# Remute-RF-FT.net
KiCad netlist of a schematic drawn in Altium Designer
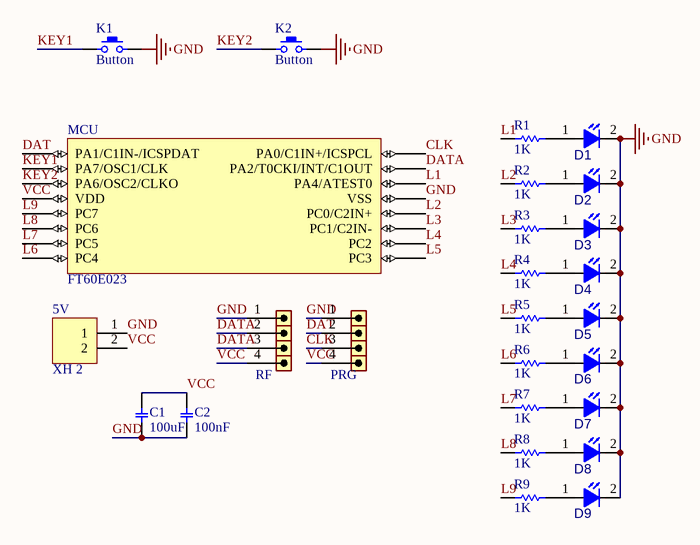
[diagram p0: Remute-RF-FT.SchDoc]

(export (version "E")
  (design (tool "Eeschema 10.0.6"))
  (components
    (comp (ref "5V")
      (value "XH 2")
      (footprint "XH 2 PIN ( White )")
      (description "Conector XH 2 Pin")
      (libsource (lib "XH Connector") (part "Conector XH 2 Pin"))
    )
    (comp (ref "C1")
      (value "100uF")
      (footprint "C1206")
      (description "Capacitor C SMD 1206")
      (fields (field (name "Comment") "Capacitor SMD 1206"))
      (libsource (lib "Capacitor") (part "Capacitor SMD 1206"))
    )
    (comp (ref "C2")
      (value "100nF")
      (footprint "C1206")
      (description "Capacitor C SMD 1206")
      (fields (field (name "Comment") "Capacitor SMD 1206"))
      (libsource (lib "Capacitor") (part "Capacitor SMD 1206"))
    )
    (comp (ref "D1")
      (value "LED SMD 1206")
      (footprint "LED SMD 1206 (Blue)")
      (libsource (lib "LED") (part "LED SMD 1206"))
    )
    (comp (ref "D2")
      (value "LED SMD 1206")
      (footprint "LED SMD 1206 (Blue)")
      (libsource (lib "LED") (part "LED SMD 1206"))
    )
    (comp (ref "D3")
      (value "LED SMD 1206")
      (footprint "LED SMD 1206 (Blue)")
      (libsource (lib "LED") (part "LED SMD 1206"))
    )
    (comp (ref "D4")
      (value "LED SMD 1206")
      (footprint "LED SMD 1206 (Blue)")
      (libsource (lib "LED") (part "LED SMD 1206"))
    )
    (comp (ref "D5")
      (value "LED SMD 1206")
      (footprint "LED SMD 1206 (Blue)")
      (libsource (lib "LED") (part "LED SMD 1206"))
    )
    (comp (ref "D6")
      (value "LED SMD 1206")
      (footprint "LED SMD 1206 (Blue)")
      (libsource (lib "LED") (part "LED SMD 1206"))
    )
    (comp (ref "D7")
      (value "LED SMD 1206")
      (footprint "LED SMD 1206 (Blue)")
      (libsource (lib "LED") (part "LED SMD 1206"))
    )
    (comp (ref "D8")
      (value "LED SMD 1206")
      (footprint "LED SMD 1206 (Blue)")
      (libsource (lib "LED") (part "LED SMD 1206"))
    )
    (comp (ref "D9")
      (value "LED SMD 1206")
      (footprint "LED SMD 1206 (Blue)")
      (libsource (lib "LED") (part "LED SMD 1206"))
    )
    (comp (ref "K1")
      (value "Button")
      (footprint "BUTTON")
      (fields
        (field (name "MANUFACTURER") "Panasonic")
        (field (name "MANUFACTURER PART NUMBER") "EVQ-PE605T")
      )
      (libsource (lib "LIBM") (part "BUTTON-6.3.4-SMD"))
    )
    (comp (ref "K2")
      (value "Button")
      (footprint "BUTTON")
      (fields
        (field (name "MANUFACTURER") "Panasonic")
        (field (name "MANUFACTURER PART NUMBER") "EVQ-PE605T")
      )
      (libsource (lib "LIBM") (part "BUTTON-6.3.4-SMD"))
    )
    (comp (ref "MCU") (value "FT60E023") (footprint "SSOP-16") (libsource (lib "HOLTEK") (part "FT60E023")))
    (comp (ref "PRG")
      (value "Female Header Single 4")
      (footprint "HDR_F_1X4")
      (description "Female, pitch: 2.54mm")
      (libsource (lib "Header") (part "Female Header Single 4"))
    )
    (comp (ref "R1")
      (value "1K")
      (footprint "R0805")
      (description "Resistor SMD 0805")
      (libsource (lib "Resistor") (part "Resistor SMD 0805"))
    )
    (comp (ref "R2")
      (value "1K")
      (footprint "R0805")
      (description "Resistor SMD 0805")
      (libsource (lib "Resistor") (part "Resistor SMD 0805"))
    )
    (comp (ref "R3")
      (value "1K")
      (footprint "R0805")
      (description "Resistor SMD 0805")
      (libsource (lib "Resistor") (part "Resistor SMD 0805"))
    )
    (comp (ref "R4")
      (value "1K")
      (footprint "R0805")
      (description "Resistor SMD 0805")
      (libsource (lib "Resistor") (part "Resistor SMD 0805"))
    )
    (comp (ref "R5")
      (value "1K")
      (footprint "R0805")
      (description "Resistor SMD 0805")
      (libsource (lib "Resistor") (part "Resistor SMD 0805"))
    )
    (comp (ref "R6")
      (value "1K")
      (footprint "R0805")
      (description "Resistor SMD 0805")
      (libsource (lib "Resistor") (part "Resistor SMD 0805"))
    )
    (comp (ref "R7")
      (value "1K")
      (footprint "R0805")
      (description "Resistor SMD 0805")
      (libsource (lib "Resistor") (part "Resistor SMD 0805"))
    )
    (comp (ref "R8")
      (value "1K")
      (footprint "R0805")
      (description "Resistor SMD 0805")
      (libsource (lib "Resistor") (part "Resistor SMD 0805"))
    )
    (comp (ref "R9")
      (value "1K")
      (footprint "R0805")
      (description "Resistor SMD 0805")
      (libsource (lib "Resistor") (part "Resistor SMD 0805"))
    )
    (comp (ref "RF")
      (value "Female Header Single 4")
      (footprint "HDR_F_1X4")
      (description "Female, pitch: 2.54mm")
      (libsource (lib "Header") (part "Female Header Single 4"))
    )
  )
  (nets
    (net (code "1") (name "/CLK") (class "Default")
      (node (ref "MCU") (pin "16") (pinfunction "PA0/C1IN+/ICSPCL_16") (pintype "bidirectional"))
      (node (ref "PRG") (pin "3") (pinfunction "3_3") (pintype "passive"))
    )
    (net (code "2") (name "/DAT") (class "Default")
      (node (ref "MCU") (pin "1") (pinfunction "PA1/C1IN-/ICSPDAT_1") (pintype "bidirectional"))
      (node (ref "PRG") (pin "2") (pinfunction "2_2") (pintype "passive"))
    )
    (net (code "3") (name "/DATA") (class "Default")
      (node (ref "MCU") (pin "15") (pinfunction "PA2/T0CKI/INT/C1OUT_15") (pintype "bidirectional"))
      (node (ref "RF") (pin "2") (pinfunction "2_2") (pintype "passive"))
      (node (ref "RF") (pin "3") (pinfunction "3_3") (pintype "passive"))
    )
    (net (code "4") (name "/KEY1") (class "Default")
      (node (ref "K1") (pin "1") (pinfunction "1_1") (pintype "passive"))
      (node (ref "MCU") (pin "2") (pinfunction "PA7/OSC1/CLK_2") (pintype "bidirectional"))
    )
    (net (code "5") (name "/KEY2") (class "Default")
      (node (ref "K2") (pin "1") (pinfunction "1_1") (pintype "passive"))
      (node (ref "MCU") (pin "3") (pinfunction "PA6/OSC2/CLKO_3") (pintype "bidirectional"))
    )
    (net (code "6") (name "/L1") (class "Default")
      (node (ref "MCU") (pin "14") (pinfunction "PA4/ATEST0_14") (pintype "bidirectional"))
      (node (ref "R1") (pin "1") (pinfunction "1_1") (pintype "passive"))
    )
    (net (code "7") (name "/L2") (class "Default")
      (node (ref "MCU") (pin "12") (pinfunction "PC0/C2IN+_12") (pintype "bidirectional"))
      (node (ref "R2") (pin "1") (pinfunction "1_1") (pintype "passive"))
    )
    (net (code "8") (name "/L3") (class "Default")
      (node (ref "MCU") (pin "11") (pinfunction "PC1/C2IN-_11") (pintype "bidirectional"))
      (node (ref "R3") (pin "1") (pinfunction "1_1") (pintype "passive"))
    )
    (net (code "9") (name "/L4") (class "Default")
      (node (ref "MCU") (pin "10") (pinfunction "PC2_10") (pintype "bidirectional"))
      (node (ref "R4") (pin "1") (pinfunction "1_1") (pintype "passive"))
    )
    (net (code "10") (name "/L5") (class "Default")
      (node (ref "MCU") (pin "9") (pinfunction "PC3_9") (pintype "bidirectional"))
      (node (ref "R5") (pin "1") (pinfunction "1_1") (pintype "passive"))
    )
    (net (code "11") (name "/L6") (class "Default")
      (node (ref "MCU") (pin "8") (pinfunction "PC4_8") (pintype "bidirectional"))
      (node (ref "R6") (pin "1") (pinfunction "1_1") (pintype "passive"))
    )
    (net (code "12") (name "/L7") (class "Default")
      (node (ref "MCU") (pin "7") (pinfunction "PC5_7") (pintype "bidirectional"))
      (node (ref "R7") (pin "1") (pinfunction "1_1") (pintype "passive"))
    )
    (net (code "13") (name "/L8") (class "Default")
      (node (ref "MCU") (pin "6") (pinfunction "PC6_6") (pintype "bidirectional"))
      (node (ref "R8") (pin "1") (pinfunction "1_1") (pintype "passive"))
    )
    (net (code "14") (name "/L9") (class "Default")
      (node (ref "MCU") (pin "5") (pinfunction "PC7_5") (pintype "bidirectional"))
      (node (ref "R9") (pin "1") (pinfunction "1_1") (pintype "passive"))
    )
    (net (code "15") (name "/VCC") (class "Default")
      (node (ref "5V") (pin "2") (pinfunction "2_2") (pintype "passive"))
      (node (ref "C1") (pin "2") (pinfunction "2_2") (pintype "passive"))
      (node (ref "C2") (pin "2") (pinfunction "2_2") (pintype "passive"))
      (node (ref "MCU") (pin "4") (pinfunction "VDD_4") (pintype "bidirectional"))
      (node (ref "PRG") (pin "4") (pinfunction "4_4") (pintype "passive"))
      (node (ref "RF") (pin "4") (pinfunction "4_4") (pintype "passive"))
    )
    (net (code "16") (name "GND") (class "Default")
      (node (ref "5V") (pin "1") (pinfunction "1_1") (pintype "passive"))
      (node (ref "C1") (pin "1") (pinfunction "1_1") (pintype "passive"))
      (node (ref "C2") (pin "1") (pinfunction "1_1") (pintype "passive"))
      (node (ref "D1") (pin "2") (pinfunction "CATHODE_2") (pintype "passive"))
      (node (ref "D2") (pin "2") (pinfunction "CATHODE_2") (pintype "passive"))
      (node (ref "D3") (pin "2") (pinfunction "CATHODE_2") (pintype "passive"))
      (node (ref "D4") (pin "2") (pinfunction "CATHODE_2") (pintype "passive"))
      (node (ref "D5") (pin "2") (pinfunction "CATHODE_2") (pintype "passive"))
      (node (ref "D6") (pin "2") (pinfunction "CATHODE_2") (pintype "passive"))
      (node (ref "D7") (pin "2") (pinfunction "CATHODE_2") (pintype "passive"))
      (node (ref "D8") (pin "2") (pinfunction "CATHODE_2") (pintype "passive"))
      (node (ref "D9") (pin "2") (pinfunction "CATHODE_2") (pintype "passive"))
      (node (ref "K1") (pin "2") (pinfunction "2_2") (pintype "passive"))
      (node (ref "K2") (pin "2") (pinfunction "2_2") (pintype "passive"))
      (node (ref "MCU") (pin "13") (pinfunction "VSS_13") (pintype "bidirectional"))
      (node (ref "PRG") (pin "1") (pinfunction "1_1") (pintype "passive"))
      (node (ref "RF") (pin "1") (pinfunction "1_1") (pintype "passive"))
    )
    (net (code "17") (name "Net-(D1-ANODE)") (class "Default")
      (node (ref "D1") (pin "1") (pinfunction "ANODE_1") (pintype "passive"))
      (node (ref "R1") (pin "2") (pinfunction "2_2") (pintype "passive"))
    )
    (net (code "18") (name "Net-(D2-ANODE)") (class "Default")
      (node (ref "D2") (pin "1") (pinfunction "ANODE_1") (pintype "passive"))
      (node (ref "R2") (pin "2") (pinfunction "2_2") (pintype "passive"))
    )
    (net (code "19") (name "Net-(D3-ANODE)") (class "Default")
      (node (ref "D3") (pin "1") (pinfunction "ANODE_1") (pintype "passive"))
      (node (ref "R3") (pin "2") (pinfunction "2_2") (pintype "passive"))
    )
    (net (code "20") (name "Net-(D4-ANODE)") (class "Default")
      (node (ref "D4") (pin "1") (pinfunction "ANODE_1") (pintype "passive"))
      (node (ref "R4") (pin "2") (pinfunction "2_2") (pintype "passive"))
    )
    (net (code "21") (name "Net-(D5-ANODE)") (class "Default")
      (node (ref "D5") (pin "1") (pinfunction "ANODE_1") (pintype "passive"))
      (node (ref "R5") (pin "2") (pinfunction "2_2") (pintype "passive"))
    )
    (net (code "22") (name "Net-(D6-ANODE)") (class "Default")
      (node (ref "D6") (pin "1") (pinfunction "ANODE_1") (pintype "passive"))
      (node (ref "R6") (pin "2") (pinfunction "2_2") (pintype "passive"))
    )
    (net (code "23") (name "Net-(D7-ANODE)") (class "Default")
      (node (ref "D7") (pin "1") (pinfunction "ANODE_1") (pintype "passive"))
      (node (ref "R7") (pin "2") (pinfunction "2_2") (pintype "passive"))
    )
    (net (code "24") (name "Net-(D8-ANODE)") (class "Default")
      (node (ref "D8") (pin "1") (pinfunction "ANODE_1") (pintype "passive"))
      (node (ref "R8") (pin "2") (pinfunction "2_2") (pintype "passive"))
    )
    (net (code "25") (name "Net-(D9-ANODE)") (class "Default")
      (node (ref "D9") (pin "1") (pinfunction "ANODE_1") (pintype "passive"))
      (node (ref "R9") (pin "2") (pinfunction "2_2") (pintype "passive"))
    )
  )
)
